# RF_Triangulation_Receiver.net
KiCad netlist of a schematic drawn in Altium Designer
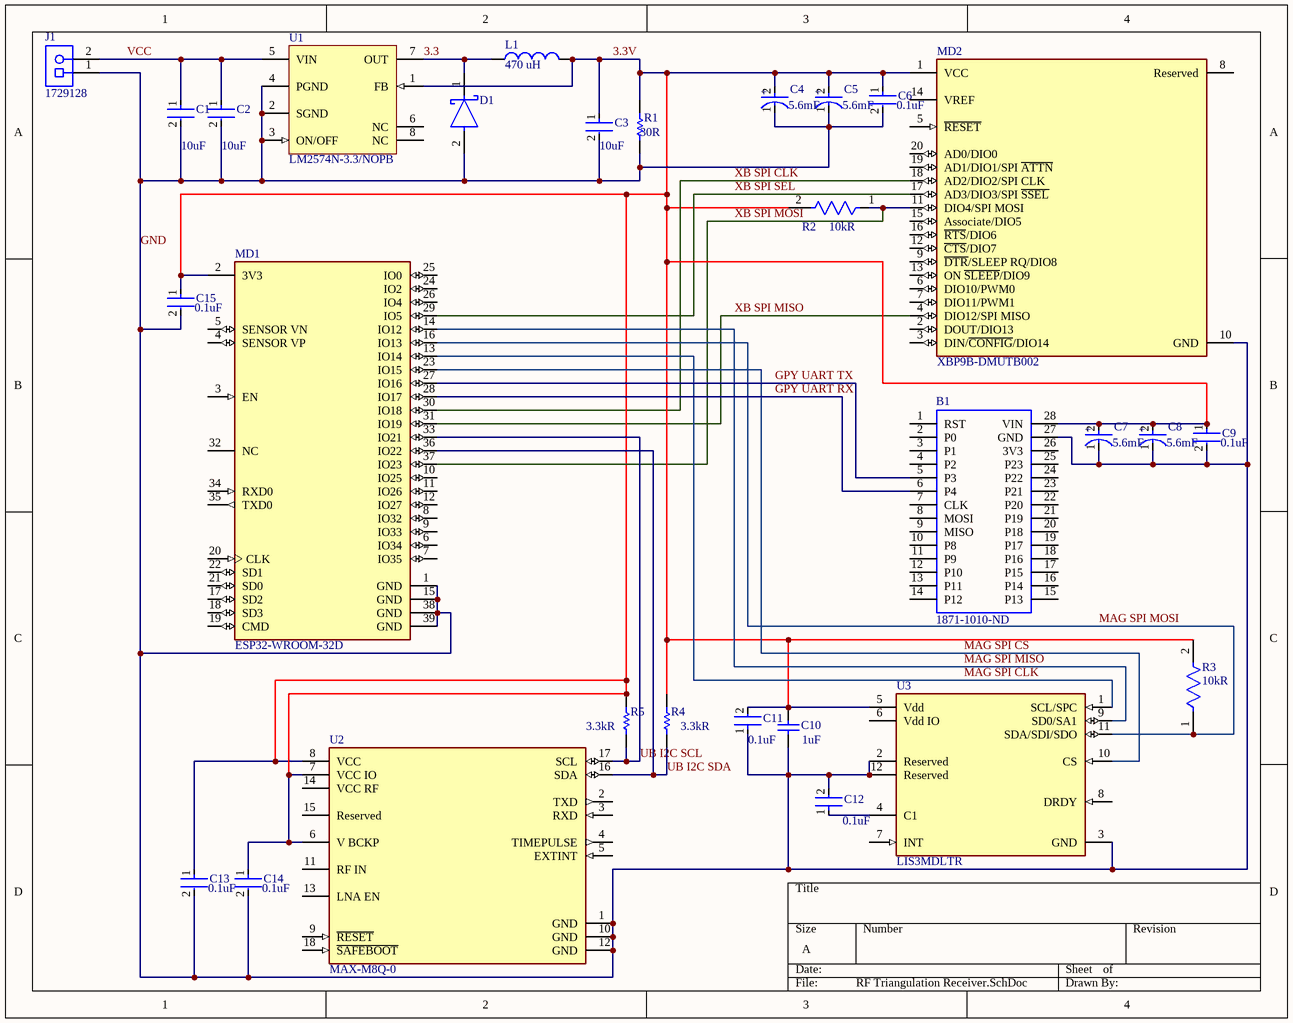
[diagram p0: RF Triangulation Receiver.SchDoc]

(export (version "E")
  (design (tool "Eeschema 10.0.6"))
  (components
    (comp (ref "B1")
      (value "1871-1010-ND")
      (footprint "18711010ND")
      (libsource (lib "1871-1010-ND") (part "1871-1010-ND"))
    )
    (comp (ref "C1")
      (value "RDEC71E106K2K1H03B")
      (footprint "FP-RDE2M1-MFG")
      (description "Ceramic Capacitor 10uF ±10% 25V X7S Radial")
      (fields (field (name "TOLERANCE") "10%") (field (name "CAPACITANCE") "10uF"))
      (libsource (lib "Altium Content Vault") (part "b4654b650e69147ec39a6b967a45e02"))
    )
    (comp (ref "C2")
      (value "RDEC71E106K2K1H03B")
      (footprint "FP-RDE2M1-MFG")
      (description "Ceramic Capacitor 10uF ±10% 25V X7S Radial")
      (fields (field (name "TOLERANCE") "10%") (field (name "CAPACITANCE") "10uF"))
      (libsource (lib "Altium Content Vault") (part "b4654b650e69147ec39a6b967a45e02"))
    )
    (comp (ref "C3")
      (value "RDEC71E106K2K1H03B")
      (footprint "FP-RDE2M1-MFG")
      (description "Ceramic Capacitor 10uF ±10% 25V X7S Radial")
      (fields (field (name "TOLERANCE") "10%") (field (name "CAPACITANCE") "10uF"))
      (libsource (lib "Altium Content Vault") (part "b4654b650e69147ec39a6b967a45e02"))
    )
    (comp (ref "C4")
      (value "EEUFM0J562S")
      (footprint "FP-RAD-TH-D_16_0_5-L_20_2-MFG")
      (description "Aluminum Electrolytic Capacitors (Radial Lead Type) 5600uF ±20% 6.3V")
      (fields
        (field (name "TOLERANCE") "20%")
        (field (name "VOLTAGE") "6.3V")
        (field (name "CAPACITANCE") "5.6mF")
      )
      (libsource (lib "Altium Content Vault") (part "203bc49f2ac43e59fd269a8c329ed05"))
    )
    (comp (ref "C5")
      (value "EEUFM0J562S")
      (footprint "FP-RAD-TH-D_16_0_5-L_20_2-MFG")
      (description "Aluminum Electrolytic Capacitors (Radial Lead Type) 5600uF ±20% 6.3V")
      (fields
        (field (name "TOLERANCE") "20%")
        (field (name "VOLTAGE") "6.3V")
        (field (name "CAPACITANCE") "5.6mF")
      )
      (libsource (lib "Altium Content Vault") (part "203bc49f2ac43e59fd269a8c329ed05"))
    )
    (comp (ref "C6")
      (value "RCER71E104K0K1H03B")
      (footprint "FP-RCE0K1-MFG")
      (description "Cap Ceramic 100nF 25V X7R ±10% Radial 5mm +125°C Automotive Bulk")
      (fields (field (name "CAPACITANCE") "0.1uF"))
      (libsource (lib "Altium Content Vault") (part "b4654b650e69147ec39a6b967a45e02"))
    )
    (comp (ref "C7")
      (value "EEUFM0J562S")
      (footprint "FP-RAD-TH-D_16_0_5-L_20_2-MFG")
      (description "Aluminum Electrolytic Capacitors (Radial Lead Type) 5600uF ±20% 6.3V")
      (fields
        (field (name "TOLERANCE") "20%")
        (field (name "VOLTAGE") "6.3V")
        (field (name "CAPACITANCE") "5.6mF")
      )
      (libsource (lib "Altium Content Vault") (part "203bc49f2ac43e59fd269a8c329ed05"))
    )
    (comp (ref "C8")
      (value "EEUFM0J562S")
      (footprint "FP-RAD-TH-D_16_0_5-L_20_2-MFG")
      (description "Aluminum Electrolytic Capacitors (Radial Lead Type) 5600uF ±20% 6.3V")
      (fields
        (field (name "TOLERANCE") "20%")
        (field (name "VOLTAGE") "6.3V")
        (field (name "CAPACITANCE") "5.6mF")
      )
      (libsource (lib "Altium Content Vault") (part "203bc49f2ac43e59fd269a8c329ed05"))
    )
    (comp (ref "C9")
      (value "RCER71E104K0K1H03B")
      (footprint "FP-RCE0K1-MFG")
      (description "Cap Ceramic 100nF 25V X7R ±10% Radial 5mm +125°C Automotive Bulk")
      (fields (field (name "CAPACITANCE") "0.1uF"))
      (libsource (lib "Altium Content Vault") (part "b4654b650e69147ec39a6b967a45e02"))
    )
    (comp (ref "C10")
      (value "0805YC105JAT2A")
      (footprint "CAPC2013X140X50ML20T25")
      (fields (field (name "MANUFACTURER") "AVX Interconnect / Elco") (field (name "CAPACITANCE") "1uF"))
      (libsource (lib "Altium Content Vault") (part "CAP"))
    )
    (comp (ref "C11")
      (value "RCER71E104K0K1H03B")
      (footprint "FP-RCE0K1-MFG")
      (description "Cap Ceramic 100nF 25V X7R ±10% Radial 5mm +125°C Automotive Bulk")
      (fields (field (name "CAPACITANCE") "0.1uF"))
      (libsource (lib "Altium Content Vault") (part "b4654b650e69147ec39a6b967a45e02"))
    )
    (comp (ref "C12")
      (value "RCER71E104K0K1H03B")
      (footprint "FP-RCE0K1-MFG")
      (description "Cap Ceramic 100nF 25V X7R ±10% Radial 5mm +125°C Automotive Bulk")
      (fields (field (name "CAPACITANCE") "0.1uF"))
      (libsource (lib "Altium Content Vault") (part "b4654b650e69147ec39a6b967a45e02"))
    )
    (comp (ref "C13")
      (value "RCER71E104K0K1H03B")
      (footprint "FP-RCE0K1-MFG")
      (description "Cap Ceramic 100nF 25V X7R ±10% Radial 5mm +125°C Automotive Bulk")
      (fields (field (name "CAPACITANCE") "0.1uF"))
      (libsource (lib "Altium Content Vault") (part "b4654b650e69147ec39a6b967a45e02"))
    )
    (comp (ref "C14")
      (value "RCER71E104K0K1H03B")
      (footprint "FP-RCE0K1-MFG")
      (description "Cap Ceramic 100nF 25V X7R ±10% Radial 5mm +125°C Automotive Bulk")
      (fields (field (name "CAPACITANCE") "0.1uF"))
      (libsource (lib "Altium Content Vault") (part "b4654b650e69147ec39a6b967a45e02"))
    )
    (comp (ref "C15")
      (value "RCER71E104K0K1H03B")
      (footprint "FP-RCE0K1-MFG")
      (description "Cap Ceramic 100nF 25V X7R ±10% Radial 5mm +125°C Automotive Bulk")
      (fields (field (name "CAPACITANCE") "0.1uF"))
      (libsource (lib "Altium Content Vault") (part "b4654b650e69147ec39a6b967a45e02"))
    )
    (comp (ref "D1")
      (value "BAT60AE6327HTSA1")
      (footprint "FP-PG-SOD323-2-IPC_C")
      (description "DIODE SCHOTTKY 10V 3A SOD323-2")
      (libsource (lib "Altium Content Vault") (part "1d6ec82d83fb6aee721767c19dac4b9"))
    )
    (comp (ref "J1")
      (value "1729128")
      (footprint "PHOE-1729128-2_V")
      (description "PCB Terminal Block, 13.5 A, 400 V, 2-Pin THD, RoHS, Bulk")
      (fields (field (name "MANUFACTURER") "Phoenix Contact"))
      (libsource (lib "Altium Content Vault") (part "CN-2P-F-R2"))
    )
    (comp (ref "L1")
      (value "B78108S1474J")
      (footprint "EPCS-B78108S-2_V1")
      (description "RF Choke, 470 uH +/- 5%, 170 mA, Dia 4 mm, Length 9.2 mm, Axial Leads, RoHS, Tape and Reel")
      (fields
        (field (name "MANUFACTURER") "EPCOS")
        (field (name "TOLERANCE") "+/- 5%")
        (field (name "LR") "470 uH")
      )
      (libsource (lib "Altium Content Vault") (part "EPCS-IND-2"))
    )
    (comp (ref "MD1")
      (value "ESP32-WROOM-32D")
      (footprint "FP-ESP32-WROOM-32D-MFG")
      (description "WIFI MODULE 32MBITS SPI FLASH")
      (fields
        (field (name "OCTOPART") "https://octopart.com/esp32-wroom-32d-espressif+systems-91040050")
        (field (name "MANUFACTURER") "Espressif Systems")
      )
      (libsource (lib "Altium Content Vault") (part "a031a76f8c27026a7a7f4657ff233a3"))
    )
    (comp (ref "MD2")
      (value "XBP9B-DMUTB002")
      (footprint "FP-XBP9B-DMUTB002-MFG")
      (description "RX TXRX MOD ISM < 1GHZ U.FL TH")
      (libsource (lib "Altium Content Vault") (part "053d8e65a610ce00d52093c0e212ca3"))
    )
    (comp (ref "R1")
      (value "ERJ-2RKF30R0X")
      (footprint "RESC1005X40X25LL05T05")
      (fields (field (name "MANUFACTURER") "Panasonic") (field (name "RESISTANCE") "30R"))
      (libsource (lib "Altium Content Vault") (part "RES"))
    )
    (comp (ref "R2")
      (value "CR0805-FX-1002ELF")
      (footprint "FP-CR0805-IPC_A")
      (description "Thick Film Chip Resistors 0805 10kΩ 0.125W 1% 100ppm/°C")
      (fields (field (name "TOLERANCE") "1%") (field (name "RESISTANCE") "10kR"))
      (libsource (lib "Altium Content Vault") (part "1029c3af85768c4190bb7ad29bc67b5"))
    )
    (comp (ref "R3")
      (value "CR0805-FX-1002ELF")
      (footprint "FP-CR0805-IPC_A")
      (description "Thick Film Chip Resistors 0805 10kΩ 0.125W 1% 100ppm/°C")
      (fields (field (name "TOLERANCE") "1%") (field (name "RESISTANCE") "10kR"))
      (libsource (lib "Altium Content Vault") (part "1029c3af85768c4190bb7ad29bc67b5"))
    )
    (comp (ref "R4")
      (value "RK73H1JTTD3301F")
      (footprint "RESC1608X55X30NL20T10")
      (fields (field (name "MANUFACTURER") "KOA Speer") (field (name "RESISTANCE") "3.3kR"))
      (libsource (lib "Altium Content Vault") (part "RES"))
    )
    (comp (ref "R5")
      (value "RK73H1JTTD3301F")
      (footprint "RESC1608X55X30NL20T10")
      (fields (field (name "MANUFACTURER") "KOA Speer") (field (name "RESISTANCE") "3.3kR"))
      (libsource (lib "Altium Content Vault") (part "RES"))
    )
    (comp (ref "U1")
      (value "LM2574N-3.3/NOPB")
      (footprint "P0008A")
      (description "SIMPLE SWITCHER® 0.5A Step-Down Voltage Regulator, 8-pin MDIP, Pb-Free")
      (fields (field (name "MANUFACTURER") "Texas Instruments"))
      (libsource (lib "Altium Content Vault") (part "PM-REG-LM2574HVN-12"))
    )
    (comp (ref "U2")
      (value "MAX-M8Q-0")
      (footprint "FP-MAX-M8Q-0-MFG")
      (description "RF RCVR GNSS/GPS 1.575GHZ 18LCC")
      (libsource (lib "Altium Content Vault") (part "3a4eaf80b39255b10f8ea21395ff7da"))
    )
    (comp (ref "U3")
      (value "LIS3MDLTR")
      (footprint "FP-VFLGA-12-8365767-MFG")
      (description "SENSOR MR I2C/SPI 12LGA")
      (fields
        (field (name "OCTOPART") "https://octopart.com/lis3mdltr-stmicroelectronics-29403125")
        (field (name "MANUFACTURER") "STMicroelectronics")
      )
      (libsource (lib "Altium Content Vault") (part "41c0331d4207a07573b21020ef49d7d"))
    )
  )
  (nets
    (net (code "1") (name "/3.3") (class "Default")
      (node (ref "D1") (pin "1") (pinfunction "C_1") (pintype "passive"))
      (node (ref "L1") (pin "1") (pinfunction "1_1") (pintype "passive"))
      (node (ref "U1") (pin "7") (pinfunction "OUT_7") (pintype "power_in"))
    )
    (net (code "2") (name "/3.3V") (class "Default")
      (node (ref "B1") (pin "28") (pinfunction "VIN_28") (pintype "passive"))
      (node (ref "C10") (pin "2") (pinfunction "2_2") (pintype "passive"))
      (node (ref "C11") (pin "2") (pinfunction "2_2") (pintype "passive"))
      (node (ref "C13") (pin "1") (pinfunction "1_1") (pintype "passive"))
      (node (ref "C14") (pin "1") (pinfunction "1_1") (pintype "passive"))
      (node (ref "C15") (pin "1") (pinfunction "1_1") (pintype "passive"))
      (node (ref "C3") (pin "1") (pinfunction "1_1") (pintype "passive"))
      (node (ref "C4") (pin "2") (pinfunction "A_2") (pintype "passive"))
      (node (ref "C5") (pin "2") (pinfunction "A_2") (pintype "passive"))
      (node (ref "C6") (pin "1") (pinfunction "1_1") (pintype "passive"))
      (node (ref "C7") (pin "2") (pinfunction "A_2") (pintype "passive"))
      (node (ref "C8") (pin "2") (pinfunction "A_2") (pintype "passive"))
      (node (ref "C9") (pin "1") (pinfunction "1_1") (pintype "passive"))
      (node (ref "L1") (pin "2") (pinfunction "2_2") (pintype "passive"))
      (node (ref "MD1") (pin "2") (pinfunction "3V3_2") (pintype "power_in"))
      (node (ref "MD2") (pin "1") (pinfunction "VCC_1") (pintype "power_in"))
      (node (ref "R1") (pin "2") (pinfunction "2_2") (pintype "passive"))
      (node (ref "R2") (pin "2") (pinfunction "2_2") (pintype "passive"))
      (node (ref "R3") (pin "2") (pinfunction "2_2") (pintype "passive"))
      (node (ref "R4") (pin "2") (pinfunction "2_2") (pintype "passive"))
      (node (ref "R5") (pin "2") (pinfunction "2_2") (pintype "passive"))
      (node (ref "U1") (pin "1") (pinfunction "FB_1") (pintype "input"))
      (node (ref "U2") (pin "6") (pinfunction "V_BCKP_6") (pintype "power_in"))
      (node (ref "U2") (pin "7") (pinfunction "VCC_IO_7") (pintype "power_in"))
      (node (ref "U2") (pin "8") (pinfunction "VCC_8") (pintype "power_in"))
      (node (ref "U3") (pin "5") (pinfunction "Vdd_5") (pintype "power_in"))
    )
    (net (code "3") (name "/GND") (class "Default")
      (node (ref "B1") (pin "27") (pinfunction "GND_27") (pintype "passive"))
      (node (ref "C1") (pin "2") (pinfunction "2_2") (pintype "passive"))
      (node (ref "C10") (pin "1") (pinfunction "1_1") (pintype "passive"))
      (node (ref "C11") (pin "1") (pinfunction "1_1") (pintype "passive"))
      (node (ref "C12") (pin "2") (pinfunction "2_2") (pintype "passive"))
      (node (ref "C13") (pin "2") (pinfunction "2_2") (pintype "passive"))
      (node (ref "C14") (pin "2") (pinfunction "2_2") (pintype "passive"))
      (node (ref "C15") (pin "2") (pinfunction "2_2") (pintype "passive"))
      (node (ref "C2") (pin "2") (pinfunction "2_2") (pintype "passive"))
      (node (ref "C3") (pin "2") (pinfunction "2_2") (pintype "passive"))
      (node (ref "C4") (pin "1") (pinfunction "C_1") (pintype "passive"))
      (node (ref "C5") (pin "1") (pinfunction "C_1") (pintype "passive"))
      (node (ref "C6") (pin "2") (pinfunction "2_2") (pintype "passive"))
      (node (ref "C7") (pin "1") (pinfunction "C_1") (pintype "passive"))
      (node (ref "C8") (pin "1") (pinfunction "C_1") (pintype "passive"))
      (node (ref "C9") (pin "2") (pinfunction "2_2") (pintype "passive"))
      (node (ref "D1") (pin "2") (pinfunction "A_2") (pintype "passive"))
      (node (ref "J1") (pin "1") (pinfunction "1_1") (pintype "passive"))
      (node (ref "MD1") (pin "1") (pinfunction "GND_1") (pintype "power_in"))
      (node (ref "MD1") (pin "15") (pinfunction "GND_15") (pintype "power_in"))
      (node (ref "MD1") (pin "38") (pinfunction "GND_38") (pintype "power_in"))
      (node (ref "MD1") (pin "39") (pinfunction "GND_39") (pintype "power_in"))
      (node (ref "MD2") (pin "10") (pinfunction "GND_10") (pintype "power_in"))
      (node (ref "R1") (pin "1") (pinfunction "1_1") (pintype "passive"))
      (node (ref "U1") (pin "2") (pinfunction "SGND_2") (pintype "power_in"))
      (node (ref "U1") (pin "3") (pinfunction "ON/OFF_3") (pintype "input"))
      (node (ref "U1") (pin "4") (pinfunction "PGND_4") (pintype "power_in"))
      (node (ref "U2") (pin "1") (pinfunction "GND_1") (pintype "power_in"))
      (node (ref "U2") (pin "10") (pinfunction "GND_10") (pintype "power_in"))
      (node (ref "U2") (pin "12") (pinfunction "GND_12") (pintype "power_in"))
      (node (ref "U3") (pin "12") (pinfunction "Reserved_12") (pintype "passive"))
      (node (ref "U3") (pin "2") (pinfunction "Reserved_2") (pintype "passive"))
      (node (ref "U3") (pin "3") (pinfunction "GND_3") (pintype "power_in"))
    )
    (net (code "4") (name "/GPY UART RX") (class "Default")
      (node (ref "B1") (pin "6") (pinfunction "P4_6") (pintype "passive"))
      (node (ref "MD1") (pin "28") (pinfunction "IO17_28") (pintype "bidirectional"))
    )
    (net (code "5") (name "/GPY UART TX") (class "Default")
      (node (ref "B1") (pin "5") (pinfunction "P3_5") (pintype "passive"))
      (node (ref "MD1") (pin "27") (pinfunction "IO16_27") (pintype "bidirectional"))
    )
    (net (code "6") (name "/MAG SPI CLK") (class "Default")
      (node (ref "MD1") (pin "13") (pinfunction "IO14_13") (pintype "bidirectional"))
      (node (ref "U3") (pin "1") (pinfunction "SCL/SPC_1") (pintype "input"))
    )
    (net (code "7") (name "/MAG SPI CS") (class "Default")
      (node (ref "MD1") (pin "23") (pinfunction "IO15_23") (pintype "bidirectional"))
      (node (ref "U3") (pin "10") (pinfunction "CS_10") (pintype "input"))
    )
    (net (code "8") (name "/MAG SPI MISO") (class "Default")
      (node (ref "MD1") (pin "14") (pinfunction "IO12_14") (pintype "bidirectional"))
      (node (ref "U3") (pin "9") (pinfunction "SD0/SA1_9") (pintype "bidirectional"))
    )
    (net (code "9") (name "/MAG SPI MOSI") (class "Default")
      (node (ref "MD1") (pin "16") (pinfunction "IO13_16") (pintype "bidirectional"))
      (node (ref "R3") (pin "1") (pinfunction "1_1") (pintype "passive"))
      (node (ref "U3") (pin "11") (pinfunction "SDA/SDI/SDO_11") (pintype "bidirectional"))
    )
    (net (code "10") (name "/UB I2C SCL") (class "Default")
      (node (ref "MD1") (pin "33") (pinfunction "IO21_33") (pintype "bidirectional"))
      (node (ref "R5") (pin "1") (pinfunction "1_1") (pintype "passive"))
      (node (ref "U2") (pin "17") (pinfunction "SCL_17") (pintype "bidirectional"))
    )
    (net (code "11") (name "/UB I2C SDA") (class "Default")
      (node (ref "MD1") (pin "36") (pinfunction "IO22_36") (pintype "bidirectional"))
      (node (ref "R4") (pin "1") (pinfunction "1_1") (pintype "passive"))
      (node (ref "U2") (pin "16") (pinfunction "SDA_16") (pintype "bidirectional"))
    )
    (net (code "12") (name "/VCC") (class "Default")
      (node (ref "C1") (pin "1") (pinfunction "1_1") (pintype "passive"))
      (node (ref "C2") (pin "1") (pinfunction "1_1") (pintype "passive"))
      (node (ref "J1") (pin "2") (pinfunction "2_2") (pintype "passive"))
      (node (ref "U1") (pin "5") (pinfunction "VIN_5") (pintype "power_in"))
    )
    (net (code "13") (name "/XB SPI CLK") (class "Default")
      (node (ref "MD1") (pin "30") (pinfunction "IO18_30") (pintype "bidirectional"))
      (node (ref "MD2") (pin "18") (pinfunction "AD2/DIO2/SPI_CLK_18") (pintype "bidirectional"))
    )
    (net (code "14") (name "/XB SPI MISO") (class "Default")
      (node (ref "MD1") (pin "31") (pinfunction "IO19_31") (pintype "bidirectional"))
      (node (ref "MD2") (pin "4") (pinfunction "DIO12/SPI_MISO_4") (pintype "bidirectional"))
    )
    (net (code "15") (name "/XB SPI MOSI") (class "Default")
      (node (ref "MD1") (pin "37") (pinfunction "IO23_37") (pintype "bidirectional"))
      (node (ref "MD2") (pin "11") (pinfunction "DIO4/SPI_MOSI_11") (pintype "bidirectional"))
      (node (ref "R2") (pin "1") (pinfunction "1_1") (pintype "passive"))
    )
    (net (code "16") (name "/XB SPI SEL") (class "Default")
      (node (ref "MD1") (pin "29") (pinfunction "IO5_29") (pintype "bidirectional"))
      (node (ref "MD2") (pin "17") (pinfunction "AD3/DIO3/SPI_~{SSEL}_17") (pintype "bidirectional"))
    )
    (net (code "17") (name "Net-(U3-C1)") (class "Default")
      (node (ref "C12") (pin "1") (pinfunction "1_1") (pintype "passive"))
      (node (ref "U3") (pin "4") (pinfunction "C1_4") (pintype "passive"))
    )
    (net (code "18") (name "unconnected-(B1-3V3-Pad26)") (class "Default")
      (node (ref "B1") (pin "26") (pinfunction "3V3_26") (pintype "passive"))
    )
    (net (code "19") (name "unconnected-(B1-CLK-Pad7)") (class "Default")
      (node (ref "B1") (pin "7") (pinfunction "CLK_7") (pintype "passive"))
    )
    (net (code "20") (name "unconnected-(B1-MISO-Pad9)") (class "Default")
      (node (ref "B1") (pin "9") (pinfunction "MISO_9") (pintype "passive"))
    )
    (net (code "21") (name "unconnected-(B1-MOSI-Pad8)") (class "Default")
      (node (ref "B1") (pin "8") (pinfunction "MOSI_8") (pintype "passive"))
    )
    (net (code "22") (name "unconnected-(B1-P0-Pad2)") (class "Default")
      (node (ref "B1") (pin "2") (pinfunction "P0_2") (pintype "passive"))
    )
    (net (code "23") (name "unconnected-(B1-P1-Pad3)") (class "Default")
      (node (ref "B1") (pin "3") (pinfunction "P1_3") (pintype "passive"))
    )
    (net (code "24") (name "unconnected-(B1-P2-Pad4)") (class "Default")
      (node (ref "B1") (pin "4") (pinfunction "P2_4") (pintype "passive"))
    )
    (net (code "25") (name "unconnected-(B1-P8-Pad10)") (class "Default")
      (node (ref "B1") (pin "10") (pinfunction "P8_10") (pintype "passive"))
    )
    (net (code "26") (name "unconnected-(B1-P9-Pad11)") (class "Default")
      (node (ref "B1") (pin "11") (pinfunction "P9_11") (pintype "passive"))
    )
    (net (code "27") (name "unconnected-(B1-P10-Pad12)") (class "Default")
      (node (ref "B1") (pin "12") (pinfunction "P10_12") (pintype "passive"))
    )
    (net (code "28") (name "unconnected-(B1-P11-Pad13)") (class "Default")
      (node (ref "B1") (pin "13") (pinfunction "P11_13") (pintype "passive"))
    )
    (net (code "29") (name "unconnected-(B1-P12-Pad14)") (class "Default")
      (node (ref "B1") (pin "14") (pinfunction "P12_14") (pintype "passive"))
    )
    (net (code "30") (name "unconnected-(B1-P13-Pad15)") (class "Default")
      (node (ref "B1") (pin "15") (pinfunction "P13_15") (pintype "passive"))
    )
    (net (code "31") (name "unconnected-(B1-P14-Pad16)") (class "Default")
      (node (ref "B1") (pin "16") (pinfunction "P14_16") (pintype "passive"))
    )
    (net (code "32") (name "unconnected-(B1-P15-Pad17)") (class "Default")
      (node (ref "B1") (pin "17") (pinfunction "P15_17") (pintype "passive"))
    )
    (net (code "33") (name "unconnected-(B1-P16-Pad18)") (class "Default")
      (node (ref "B1") (pin "18") (pinfunction "P16_18") (pintype "passive"))
    )
    (net (code "34") (name "unconnected-(B1-P17-Pad19)") (class "Default")
      (node (ref "B1") (pin "19") (pinfunction "P17_19") (pintype "passive"))
    )
    (net (code "35") (name "unconnected-(B1-P18-Pad20)") (class "Default")
      (node (ref "B1") (pin "20") (pinfunction "P18_20") (pintype "passive"))
    )
    (net (code "36") (name "unconnected-(B1-P19-Pad21)") (class "Default")
      (node (ref "B1") (pin "21") (pinfunction "P19_21") (pintype "passive"))
    )
    (net (code "37") (name "unconnected-(B1-P20-Pad22)") (class "Default")
      (node (ref "B1") (pin "22") (pinfunction "P20_22") (pintype "passive"))
    )
    (net (code "38") (name "unconnected-(B1-P21-Pad23)") (class "Default")
      (node (ref "B1") (pin "23") (pinfunction "P21_23") (pintype "passive"))
    )
    (net (code "39") (name "unconnected-(B1-P22-Pad24)") (class "Default")
      (node (ref "B1") (pin "24") (pinfunction "P22_24") (pintype "passive"))
    )
    (net (code "40") (name "unconnected-(B1-P23-Pad25)") (class "Default")
      (node (ref "B1") (pin "25") (pinfunction "P23_25") (pintype "passive"))
    )
    (net (code "41") (name "unconnected-(B1-RST-Pad1)") (class "Default")
      (node (ref "B1") (pin "1") (pinfunction "RST_1") (pintype "passive"))
    )
    (net (code "42") (name "unconnected-(MD1-CLK-Pad20)") (class "Default")
      (node (ref "MD1") (pin "20") (pinfunction "CLK_20") (pintype "input"))
    )
    (net (code "43") (name "unconnected-(MD1-CMD-Pad19)") (class "Default")
      (node (ref "MD1") (pin "19") (pinfunction "CMD_19") (pintype "bidirectional"))
    )
    (net (code "44") (name "unconnected-(MD1-EN-Pad3)") (class "Default")
      (node (ref "MD1") (pin "3") (pinfunction "EN_3") (pintype "input"))
    )
    (net (code "45") (name "unconnected-(MD1-IO0-Pad25)") (class "Default")
      (node (ref "MD1") (pin "25") (pinfunction "IO0_25") (pintype "bidirectional"))
    )
    (net (code "46") (name "unconnected-(MD1-IO2-Pad24)") (class "Default")
      (node (ref "MD1") (pin "24") (pinfunction "IO2_24") (pintype "bidirectional"))
    )
    (net (code "47") (name "unconnected-(MD1-IO4-Pad26)") (class "Default")
      (node (ref "MD1") (pin "26") (pinfunction "IO4_26") (pintype "bidirectional"))
    )
    (net (code "48") (name "unconnected-(MD1-IO25-Pad10)") (class "Default")
      (node (ref "MD1") (pin "10") (pinfunction "IO25_10") (pintype "bidirectional"))
    )
    (net (code "49") (name "unconnected-(MD1-IO26-Pad11)") (class "Default")
      (node (ref "MD1") (pin "11") (pinfunction "IO26_11") (pintype "bidirectional"))
    )
    (net (code "50") (name "unconnected-(MD1-IO27-Pad12)") (class "Default")
      (node (ref "MD1") (pin "12") (pinfunction "IO27_12") (pintype "bidirectional"))
    )
    (net (code "51") (name "unconnected-(MD1-IO32-Pad8)") (class "Default")
      (node (ref "MD1") (pin "8") (pinfunction "IO32_8") (pintype "bidirectional"))
    )
    (net (code "52") (name "unconnected-(MD1-IO33-Pad9)") (class "Default")
      (node (ref "MD1") (pin "9") (pinfunction "IO33_9") (pintype "bidirectional"))
    )
    (net (code "53") (name "unconnected-(MD1-IO34-Pad6)") (class "Default")
      (node (ref "MD1") (pin "6") (pinfunction "IO34_6") (pintype "bidirectional"))
    )
    (net (code "54") (name "unconnected-(MD1-IO35-Pad7)") (class "Default")
      (node (ref "MD1") (pin "7") (pinfunction "IO35_7") (pintype "bidirectional"))
    )
    (net (code "55") (name "unconnected-(MD1-NC-Pad32)") (class "Default")
      (node (ref "MD1") (pin "32") (pinfunction "NC_32") (pintype "passive"))
    )
    (net (code "56") (name "unconnected-(MD1-RXD0-Pad34)") (class "Default")
      (node (ref "MD1") (pin "34") (pinfunction "RXD0_34") (pintype "input"))
    )
    (net (code "57") (name "unconnected-(MD1-SD0-Pad21)") (class "Default")
      (node (ref "MD1") (pin "21") (pinfunction "SD0_21") (pintype "bidirectional"))
    )
    (net (code "58") (name "unconnected-(MD1-SD1-Pad22)") (class "Default")
      (node (ref "MD1") (pin "22") (pinfunction "SD1_22") (pintype "bidirectional"))
    )
    (net (code "59") (name "unconnected-(MD1-SD2-Pad17)") (class "Default")
      (node (ref "MD1") (pin "17") (pinfunction "SD2_17") (pintype "bidirectional"))
    )
    (net (code "60") (name "unconnected-(MD1-SD3-Pad18)") (class "Default")
      (node (ref "MD1") (pin "18") (pinfunction "SD3_18") (pintype "bidirectional"))
    )
    (net (code "61") (name "unconnected-(MD1-SENSOR_VN-Pad5)") (class "Default")
      (node (ref "MD1") (pin "5") (pinfunction "SENSOR_VN_5") (pintype "bidirectional"))
    )
    (net (code "62") (name "unconnected-(MD1-SENSOR_VP-Pad4)") (class "Default")
      (node (ref "MD1") (pin "4") (pinfunction "SENSOR_VP_4") (pintype "bidirectional"))
    )
    (net (code "63") (name "unconnected-(MD1-TXD0-Pad35)") (class "Default")
      (node (ref "MD1") (pin "35") (pinfunction "TXD0_35") (pintype "output"))
    )
    (net (code "64") (name "unconnected-(MD2-AD0{slash}DIO0-Pad20)") (class "Default")
      (node (ref "MD2") (pin "20") (pinfunction "AD0/DIO0_20") (pintype "bidirectional"))
    )
    (net (code "65") (name "unconnected-(MD2-AD1{slash}DIO1{slash}SPI_~{ATTN}-Pad19)") (class "Default")
      (node (ref "MD2") (pin "19") (pinfunction "AD1/DIO1/SPI_~{ATTN}_19") (pintype "bidirectional"))
    )
    (net (code "66") (name "unconnected-(MD2-Associate{slash}DIO5-Pad15)") (class "Default")
      (node (ref "MD2") (pin "15") (pinfunction "Associate/DIO5_15") (pintype "bidirectional"))
    )
    (net (code "67") (name "unconnected-(MD2-DIN{slash}~{CONFIG}{slash}DIO14-Pad3)") (class "Default")
      (node (ref "MD2") (pin "3") (pinfunction "DIN/~{CONFIG}/DIO14_3") (pintype "bidirectional"))
    )
    (net (code "68") (name "unconnected-(MD2-DIO10{slash}PWM0-Pad6)") (class "Default")
      (node (ref "MD2") (pin "6") (pinfunction "DIO10/PWM0_6") (pintype "bidirectional"))
    )
    (net (code "69") (name "unconnected-(MD2-DIO11{slash}PWM1-Pad7)") (class "Default")
      (node (ref "MD2") (pin "7") (pinfunction "DIO11/PWM1_7") (pintype "bidirectional"))
    )
    (net (code "70") (name "unconnected-(MD2-DOUT{slash}DIO13-Pad2)") (class "Default")
      (node (ref "MD2") (pin "2") (pinfunction "DOUT/DIO13_2") (pintype "bidirectional"))
    )
    (net (code "71") (name "unconnected-(MD2-ON_~{SLEEP}{slash}DIO9-Pad13)") (class "Default")
      (node (ref "MD2") (pin "13") (pinfunction "ON_~{SLEEP}/DIO9_13") (pintype "bidirectional"))
    )
    (net (code "72") (name "unconnected-(MD2-Reserved-Pad8)") (class "Default")
      (node (ref "MD2") (pin "8") (pinfunction "Reserved_8") (pintype "passive"))
    )
    (net (code "73") (name "unconnected-(MD2-VREF-Pad14)") (class "Default")
      (node (ref "MD2") (pin "14") (pinfunction "VREF_14") (pintype "passive"))
    )
    (net (code "74") (name "unconnected-(MD2-~{CTS}{slash}DIO7-Pad12)") (class "Default")
      (node (ref "MD2") (pin "12") (pinfunction "~{CTS}/DIO7_12") (pintype "bidirectional"))
    )
    (net (code "75") (name "unconnected-(MD2-~{DTR}{slash}SLEEP_RQ{slash}DIO8-Pad9)") (class "Default")
      (node (ref "MD2") (pin "9") (pinfunction "~{DTR}/SLEEP_RQ/DIO8_9") (pintype "bidirectional"))
    )
    (net (code "76") (name "unconnected-(MD2-~{RESET}-Pad5)") (class "Default")
      (node (ref "MD2") (pin "5") (pinfunction "~{RESET}_5") (pintype "input"))
    )
    (net (code "77") (name "unconnected-(MD2-~{RTS}{slash}DIO6-Pad16)") (class "Default")
      (node (ref "MD2") (pin "16") (pinfunction "~{RTS}/DIO6_16") (pintype "bidirectional"))
    )
    (net (code "78") (name "unconnected-(U1-NC-Pad6)") (class "Default")
      (node (ref "U1") (pin "6") (pinfunction "NC_6") (pintype "passive"))
    )
    (net (code "79") (name "unconnected-(U1-NC-Pad8)") (class "Default")
      (node (ref "U1") (pin "8") (pinfunction "NC_8") (pintype "passive"))
    )
    (net (code "80") (name "unconnected-(U2-EXTINT-Pad5)") (class "Default")
      (node (ref "U2") (pin "5") (pinfunction "EXTINT_5") (pintype "input"))
    )
    (net (code "81") (name "unconnected-(U2-LNA_EN-Pad13)") (class "Default")
      (node (ref "U2") (pin "13") (pinfunction "LNA_EN_13") (pintype "passive"))
    )
    (net (code "82") (name "unconnected-(U2-RF_IN-Pad11)") (class "Default")
      (node (ref "U2") (pin "11") (pinfunction "RF_IN_11") (pintype "passive"))
    )
    (net (code "83") (name "unconnected-(U2-RXD-Pad3)") (class "Default")
      (node (ref "U2") (pin "3") (pinfunction "RXD_3") (pintype "input"))
    )
    (net (code "84") (name "unconnected-(U2-Reserved-Pad15)") (class "Default")
      (node (ref "U2") (pin "15") (pinfunction "Reserved_15") (pintype "passive"))
    )
    (net (code "85") (name "unconnected-(U2-TIMEPULSE-Pad4)") (class "Default")
      (node (ref "U2") (pin "4") (pinfunction "TIMEPULSE_4") (pintype "output"))
    )
    (net (code "86") (name "unconnected-(U2-TXD-Pad2)") (class "Default")
      (node (ref "U2") (pin "2") (pinfunction "TXD_2") (pintype "output"))
    )
    (net (code "87") (name "unconnected-(U2-VCC_RF-Pad14)") (class "Default")
      (node (ref "U2") (pin "14") (pinfunction "VCC_RF_14") (pintype "power_in"))
    )
    (net (code "88") (name "unconnected-(U2-~{RESET}-Pad9)") (class "Default")
      (node (ref "U2") (pin "9") (pinfunction "~{RESET}_9") (pintype "input"))
    )
    (net (code "89") (name "unconnected-(U2-~{SAFEBOOT}-Pad18)") (class "Default")
      (node (ref "U2") (pin "18") (pinfunction "~{SAFEBOOT}_18") (pintype "input"))
    )
    (net (code "90") (name "unconnected-(U3-DRDY-Pad8)") (class "Default")
      (node (ref "U3") (pin "8") (pinfunction "DRDY_8") (pintype "input"))
    )
    (net (code "91") (name "unconnected-(U3-INT-Pad7)") (class "Default")
      (node (ref "U3") (pin "7") (pinfunction "INT_7") (pintype "input"))
    )
    (net (code "92") (name "unconnected-(U3-Vdd_IO-Pad6)") (class "Default")
      (node (ref "U3") (pin "6") (pinfunction "Vdd_IO_6") (pintype "power_in"))
    )
  )
)
